# Signal_Detector.net
KiCad netlist of a schematic drawn in EAGLE
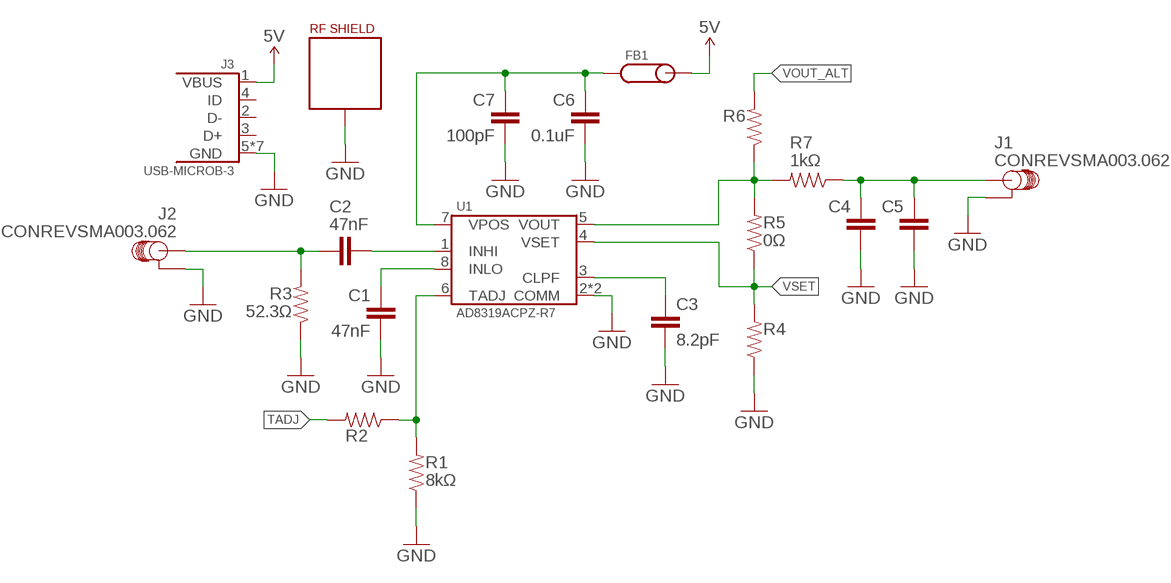
[diagram p0: schematic, sheet 1]

(export (version "E")
  (design (tool "Eeschema 10.0.6"))
  (components
    (comp (ref "C1")
      (value "47nF")
      (footprint "eagle-import:0603-CAP")
      (libsource (lib "eagle-import") (part "CAP-0603"))
    )
    (comp (ref "C2")
      (value "47nF")
      (footprint "eagle-import:0603-CAP")
      (libsource (lib "eagle-import") (part "CAP-0603"))
    )
    (comp (ref "C3")
      (value "8.2pF")
      (footprint "eagle-import:0603-CAP")
      (libsource (lib "eagle-import") (part "CAP-0603"))
    )
    (comp (ref "C4")
      (value "CAP-0603")
      (footprint "eagle-import:0603-CAP")
      (libsource (lib "eagle-import") (part "CAP-0603"))
    )
    (comp (ref "C5")
      (value "CAP-0603")
      (footprint "eagle-import:0603-CAP")
      (libsource (lib "eagle-import") (part "CAP-0603"))
    )
    (comp (ref "C6")
      (value "0.1uF")
      (footprint "eagle-import:0603-CAP")
      (libsource (lib "eagle-import") (part "CAP-0603"))
    )
    (comp (ref "C7")
      (value "100pF")
      (footprint "eagle-import:0603-CAP")
      (libsource (lib "eagle-import") (part "CAP-0603"))
    )
    (comp (ref "FB1")
      (value "FERRITE-0603")
      (footprint "eagle-import:0603-FERRITE")
      (libsource (lib "eagle-import") (part "FERRITE-0603"))
    )
    (comp (ref "J1")
      (value "CONREVSMA003.062")
      (footprint "eagle-import:SMA-EDGE")
      (libsource (lib "eagle-import") (part "SMA-EDGE"))
    )
    (comp (ref "J2")
      (value "CONREVSMA003.062")
      (footprint "eagle-import:SMA-EDGE")
      (libsource (lib "eagle-import") (part "SMA-EDGE"))
    )
    (comp (ref "J3")
      (value "USB-MICROB-3")
      (footprint "eagle-import:10118192-0001LF")
      (libsource (lib "eagle-import") (part "USB-MICROB-3"))
    )
    (comp (ref "R1")
      (value "8kΩ")
      (footprint "eagle-import:0603-CAP")
      (libsource (lib "eagle-import") (part "RESISTOR-0603"))
    )
    (comp (ref "R2")
      (value "RESISTOR-0603")
      (footprint "eagle-import:0603-CAP")
      (libsource (lib "eagle-import") (part "RESISTOR-0603"))
    )
    (comp (ref "R3")
      (value "52.3Ω")
      (footprint "eagle-import:0603-CAP")
      (libsource (lib "eagle-import") (part "RESISTOR-0603"))
    )
    (comp (ref "R4")
      (value "RESISTOR-0603")
      (footprint "eagle-import:0603-CAP")
      (libsource (lib "eagle-import") (part "RESISTOR-0603"))
    )
    (comp (ref "R5")
      (value "0Ω")
      (footprint "eagle-import:0603-CAP")
      (libsource (lib "eagle-import") (part "RESISTOR-0603"))
    )
    (comp (ref "R6")
      (value "RESISTOR-0603")
      (footprint "eagle-import:0603-CAP")
      (libsource (lib "eagle-import") (part "RESISTOR-0603"))
    )
    (comp (ref "R7")
      (value "1kΩ")
      (footprint "eagle-import:0603-CAP")
      (libsource (lib "eagle-import") (part "RESISTOR-0603"))
    )
    (comp (ref "U$1")
      (value "RF-SHIELD")
      (footprint "eagle-import:RF_SHIELD-.65X.65")
      (libsource (lib "eagle-import") (part "RF-SHIELD"))
    )
    (comp (ref "U1")
      (value "AD8319ACPZ-R7")
      (footprint "eagle-import:VFDFN-8-3X2")
      (libsource (lib "eagle-import") (part "AD8319ACPZ-R7"))
    )
  )
  (nets
    (net (code "1") (name "5V") (class "Default")
      (node (ref "FB1") (pin "P$2") (pinfunction "P$2_P$2") (pintype "bidirectional"))
      (node (ref "J3") (pin "1") (pinfunction "VBUS_1") (pintype "bidirectional"))
    )
    (net (code "2") (name "GND") (class "Default")
      (node (ref "C1") (pin "2") (pinfunction "2_2") (pintype "passive"))
      (node (ref "C3") (pin "2") (pinfunction "2_2") (pintype "passive"))
      (node (ref "C4") (pin "2") (pinfunction "2_2") (pintype "passive"))
      (node (ref "C5") (pin "2") (pinfunction "2_2") (pintype "passive"))
      (node (ref "C6") (pin "2") (pinfunction "2_2") (pintype "passive"))
      (node (ref "C7") (pin "2") (pinfunction "2_2") (pintype "passive"))
      (node (ref "J1") (pin "P$1") (pinfunction "GND_P$1") (pintype "bidirectional"))
      (node (ref "J1") (pin "P$2") (pinfunction "GND_P$2") (pintype "bidirectional"))
      (node (ref "J1") (pin "P$3") (pinfunction "GND_P$3") (pintype "bidirectional"))
      (node (ref "J1") (pin "P$4") (pinfunction "GND_P$4") (pintype "bidirectional"))
      (node (ref "J2") (pin "P$1") (pinfunction "GND_P$1") (pintype "bidirectional"))
      (node (ref "J2") (pin "P$2") (pinfunction "GND_P$2") (pintype "bidirectional"))
      (node (ref "J2") (pin "P$3") (pinfunction "GND_P$3") (pintype "bidirectional"))
      (node (ref "J2") (pin "P$4") (pinfunction "GND_P$4") (pintype "bidirectional"))
      (node (ref "J3") (pin "5") (pinfunction "GND_5") (pintype "bidirectional"))
      (node (ref "J3") (pin "P$10") (pinfunction "GND_P$10") (pintype "bidirectional"))
      (node (ref "J3") (pin "P$11") (pinfunction "GND_P$11") (pintype "bidirectional"))
      (node (ref "J3") (pin "P$6") (pinfunction "GND_P$6") (pintype "bidirectional"))
      (node (ref "J3") (pin "P$7") (pinfunction "GND_P$7") (pintype "bidirectional"))
      (node (ref "J3") (pin "P$8") (pinfunction "GND_P$8") (pintype "bidirectional"))
      (node (ref "J3") (pin "P$9") (pinfunction "GND_P$9") (pintype "bidirectional"))
      (node (ref "R1") (pin "1") (pinfunction "1_1") (pintype "passive"))
      (node (ref "R3") (pin "1") (pinfunction "1_1") (pintype "passive"))
      (node (ref "R4") (pin "1") (pinfunction "1_1") (pintype "passive"))
      (node (ref "U$1") (pin "P$1") (pinfunction "P$1_P$1") (pintype "bidirectional"))
      (node (ref "U$1") (pin "P$10") (pinfunction "P$1_P$10") (pintype "bidirectional"))
      (node (ref "U$1") (pin "P$11") (pinfunction "P$1_P$11") (pintype "bidirectional"))
      (node (ref "U$1") (pin "P$12") (pinfunction "P$1_P$12") (pintype "bidirectional"))
      (node (ref "U$1") (pin "P$2") (pinfunction "P$1_P$2") (pintype "bidirectional"))
      (node (ref "U$1") (pin "P$3") (pinfunction "P$1_P$3") (pintype "bidirectional"))
      (node (ref "U$1") (pin "P$4") (pinfunction "P$1_P$4") (pintype "bidirectional"))
      (node (ref "U$1") (pin "P$5") (pinfunction "P$1_P$5") (pintype "bidirectional"))
      (node (ref "U$1") (pin "P$6") (pinfunction "P$1_P$6") (pintype "bidirectional"))
      (node (ref "U$1") (pin "P$7") (pinfunction "P$1_P$7") (pintype "bidirectional"))
      (node (ref "U$1") (pin "P$8") (pinfunction "P$1_P$8") (pintype "bidirectional"))
      (node (ref "U$1") (pin "P$9") (pinfunction "P$1_P$9") (pintype "bidirectional"))
      (node (ref "U1") (pin "2") (pinfunction "COMM_2") (pintype "bidirectional"))
      (node (ref "U1") (pin "PAD") (pinfunction "COMM_PAD") (pintype "bidirectional"))
    )
    (net (code "3") (name "Net-(C2-Pad2)") (class "Default")
      (node (ref "C2") (pin "2") (pinfunction "2_2") (pintype "passive"))
      (node (ref "J2") (pin "SIGNAL") (pinfunction "SIGNAL_SIGNAL") (pintype "bidirectional"))
      (node (ref "R3") (pin "2") (pinfunction "2_2") (pintype "passive"))
    )
    (net (code "4") (name "Net-(C4-Pad1)") (class "Default")
      (node (ref "C4") (pin "1") (pinfunction "1_1") (pintype "passive"))
      (node (ref "C5") (pin "1") (pinfunction "1_1") (pintype "passive"))
      (node (ref "J1") (pin "SIGNAL") (pinfunction "SIGNAL_SIGNAL") (pintype "bidirectional"))
      (node (ref "R7") (pin "1") (pinfunction "1_1") (pintype "passive"))
    )
    (net (code "5") (name "Net-(U1-CLPF)") (class "Default")
      (node (ref "C3") (pin "1") (pinfunction "1_1") (pintype "passive"))
      (node (ref "U1") (pin "3") (pinfunction "CLPF_3") (pintype "bidirectional"))
    )
    (net (code "6") (name "Net-(U1-INHI)") (class "Default")
      (node (ref "C2") (pin "1") (pinfunction "1_1") (pintype "passive"))
      (node (ref "U1") (pin "1") (pinfunction "INHI_1") (pintype "bidirectional"))
    )
    (net (code "7") (name "Net-(U1-INLO)") (class "Default")
      (node (ref "C1") (pin "1") (pinfunction "1_1") (pintype "passive"))
      (node (ref "U1") (pin "8") (pinfunction "INLO_8") (pintype "bidirectional"))
    )
    (net (code "8") (name "Net-(U1-TADJ)") (class "Default")
      (node (ref "R1") (pin "2") (pinfunction "2_2") (pintype "passive"))
      (node (ref "R2") (pin "1") (pinfunction "1_1") (pintype "passive"))
      (node (ref "U1") (pin "6") (pinfunction "TADJ_6") (pintype "bidirectional"))
    )
    (net (code "9") (name "Net-(U1-VOUT)") (class "Default")
      (node (ref "R5") (pin "2") (pinfunction "2_2") (pintype "passive"))
      (node (ref "R6") (pin "1") (pinfunction "1_1") (pintype "passive"))
      (node (ref "R7") (pin "2") (pinfunction "2_2") (pintype "passive"))
      (node (ref "U1") (pin "5") (pinfunction "VOUT_5") (pintype "bidirectional"))
    )
    (net (code "10") (name "Net-(U1-VPOS)") (class "Default")
      (node (ref "C6") (pin "1") (pinfunction "1_1") (pintype "passive"))
      (node (ref "C7") (pin "1") (pinfunction "1_1") (pintype "passive"))
      (node (ref "FB1") (pin "P$1") (pinfunction "P$1_P$1") (pintype "bidirectional"))
      (node (ref "U1") (pin "7") (pinfunction "VPOS_7") (pintype "bidirectional"))
    )
    (net (code "11") (name "TADJ") (class "Default")
      (node (ref "R2") (pin "2") (pinfunction "2_2") (pintype "passive"))
    )
    (net (code "12") (name "VOUT_ALT") (class "Default")
      (node (ref "R6") (pin "2") (pinfunction "2_2") (pintype "passive"))
    )
    (net (code "13") (name "VSET") (class "Default")
      (node (ref "R4") (pin "2") (pinfunction "2_2") (pintype "passive"))
      (node (ref "R5") (pin "1") (pinfunction "1_1") (pintype "passive"))
      (node (ref "U1") (pin "4") (pinfunction "VSET_4") (pintype "bidirectional"))
    )
    (net (code "14") (name "unconnected-(J3-D+-Pad3)") (class "Default")
      (node (ref "J3") (pin "3") (pinfunction "D+_3") (pintype "bidirectional"))
    )
    (net (code "15") (name "unconnected-(J3-D--Pad2)") (class "Default")
      (node (ref "J3") (pin "2") (pinfunction "D-_2") (pintype "bidirectional"))
    )
    (net (code "16") (name "unconnected-(J3-ID-Pad4)") (class "Default")
      (node (ref "J3") (pin "4") (pinfunction "ID_4") (pintype "bidirectional"))
    )
  )
)
